# Main_board.net
KiCad netlist of a schematic drawn in EAGLE
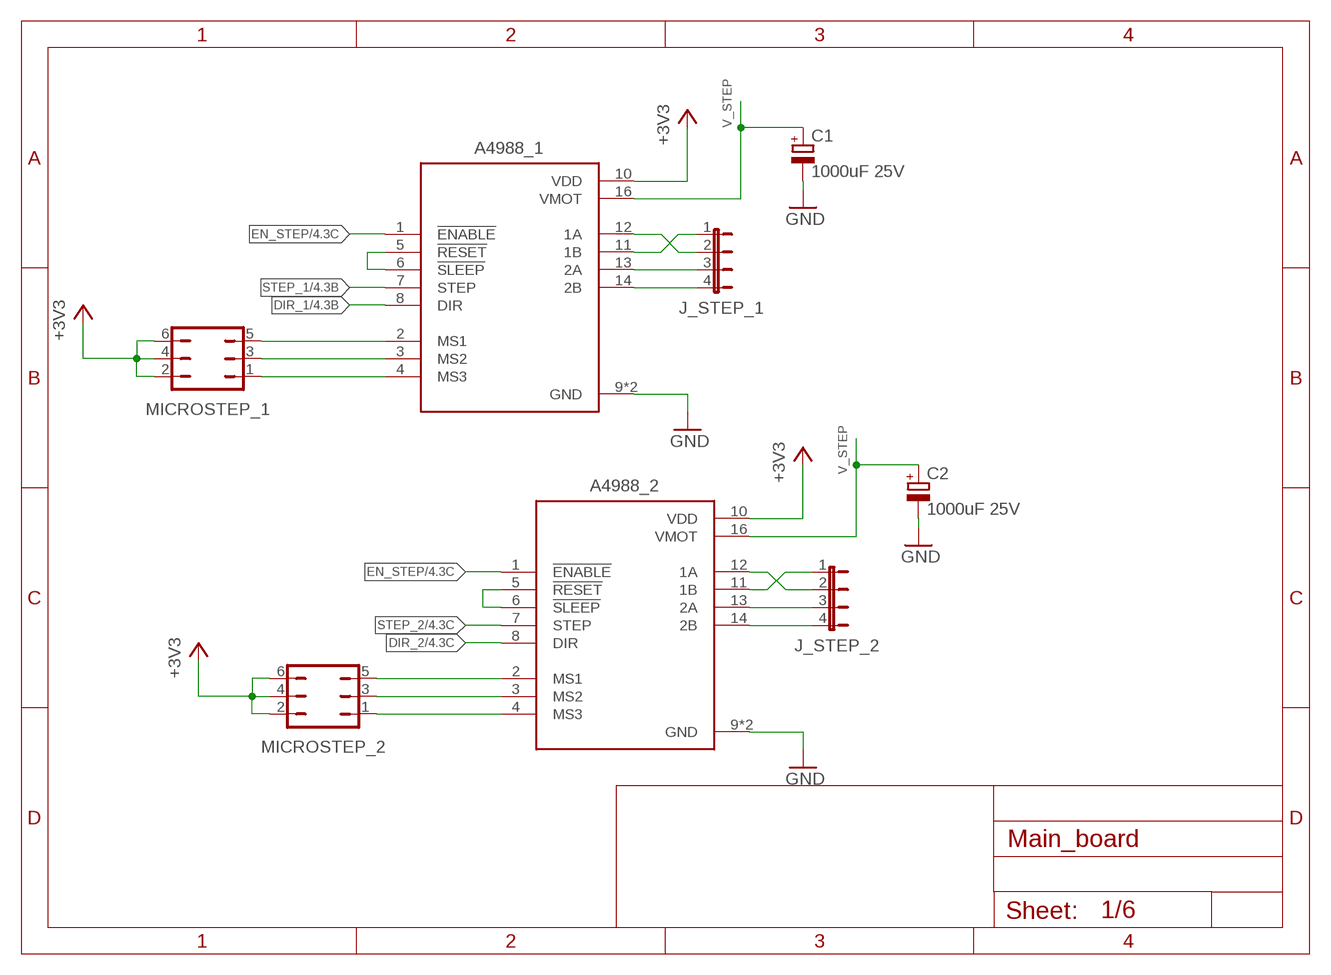
[diagram p0: schematic, sheet 1]
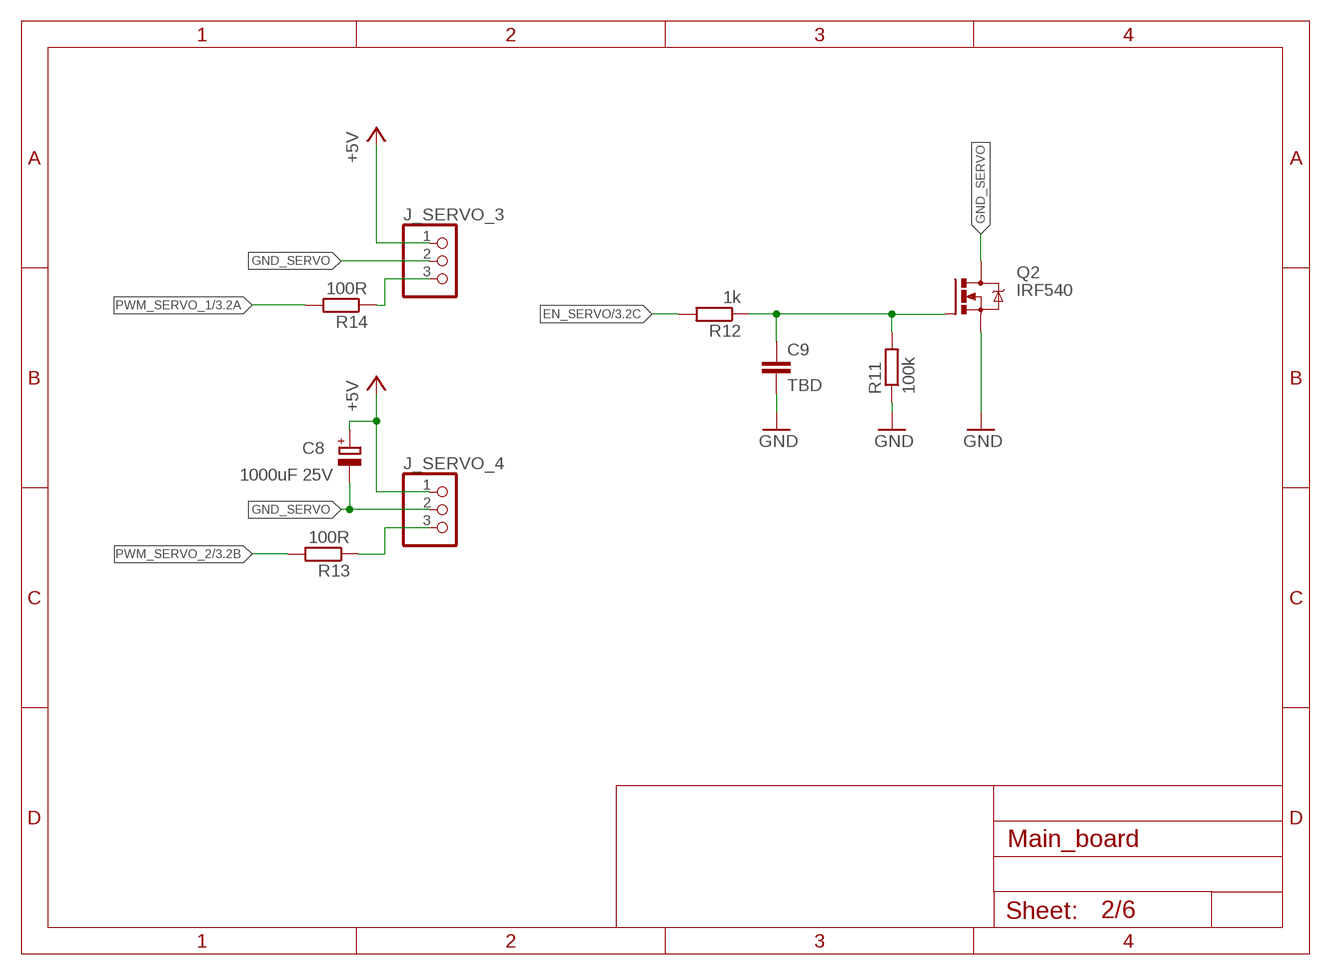
[diagram p1: schematic, sheet 2]
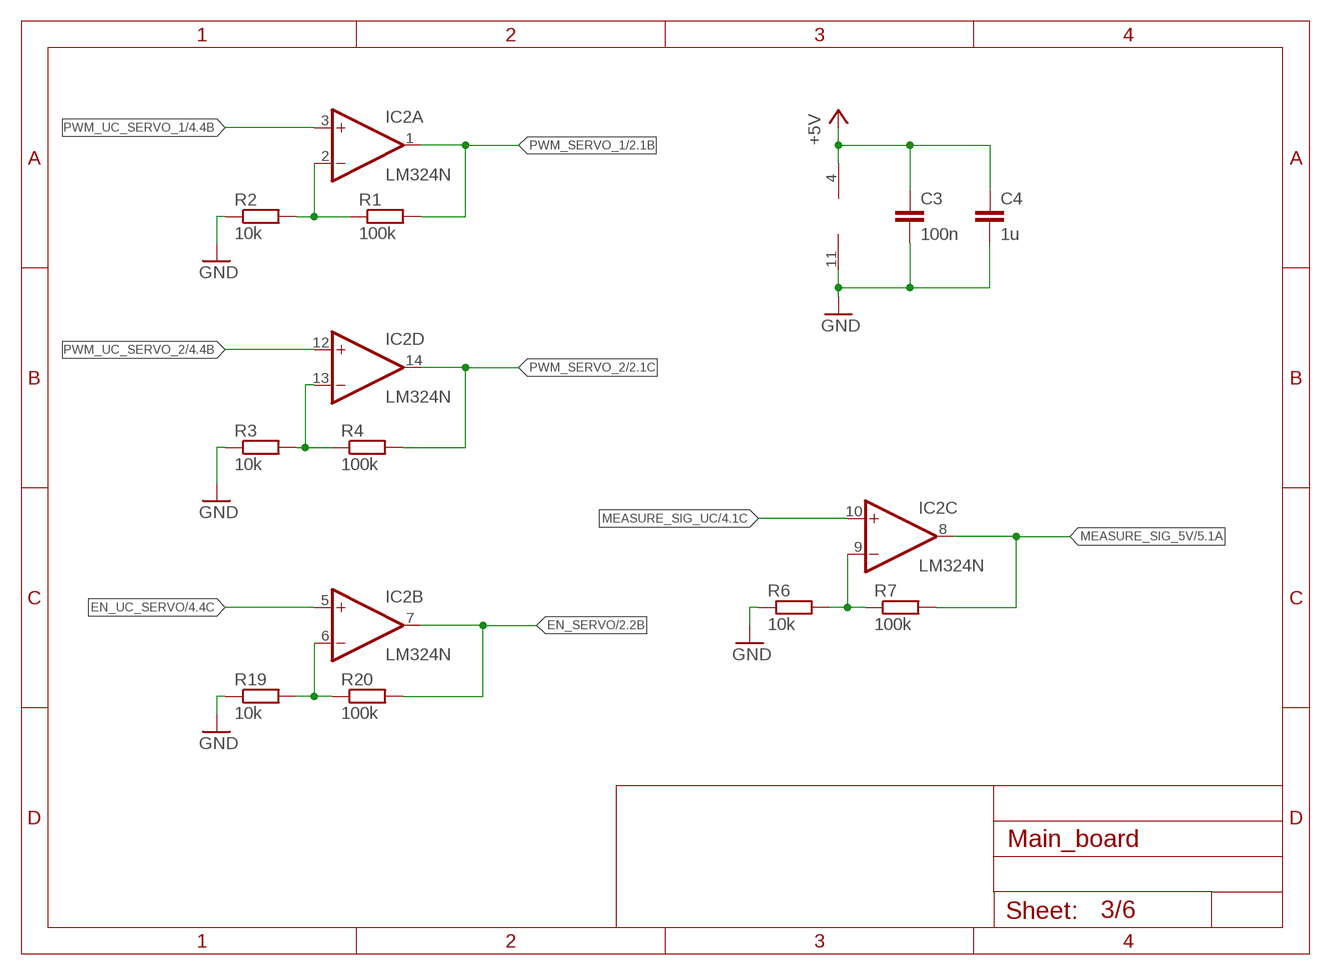
[diagram p2: schematic, sheet 3]
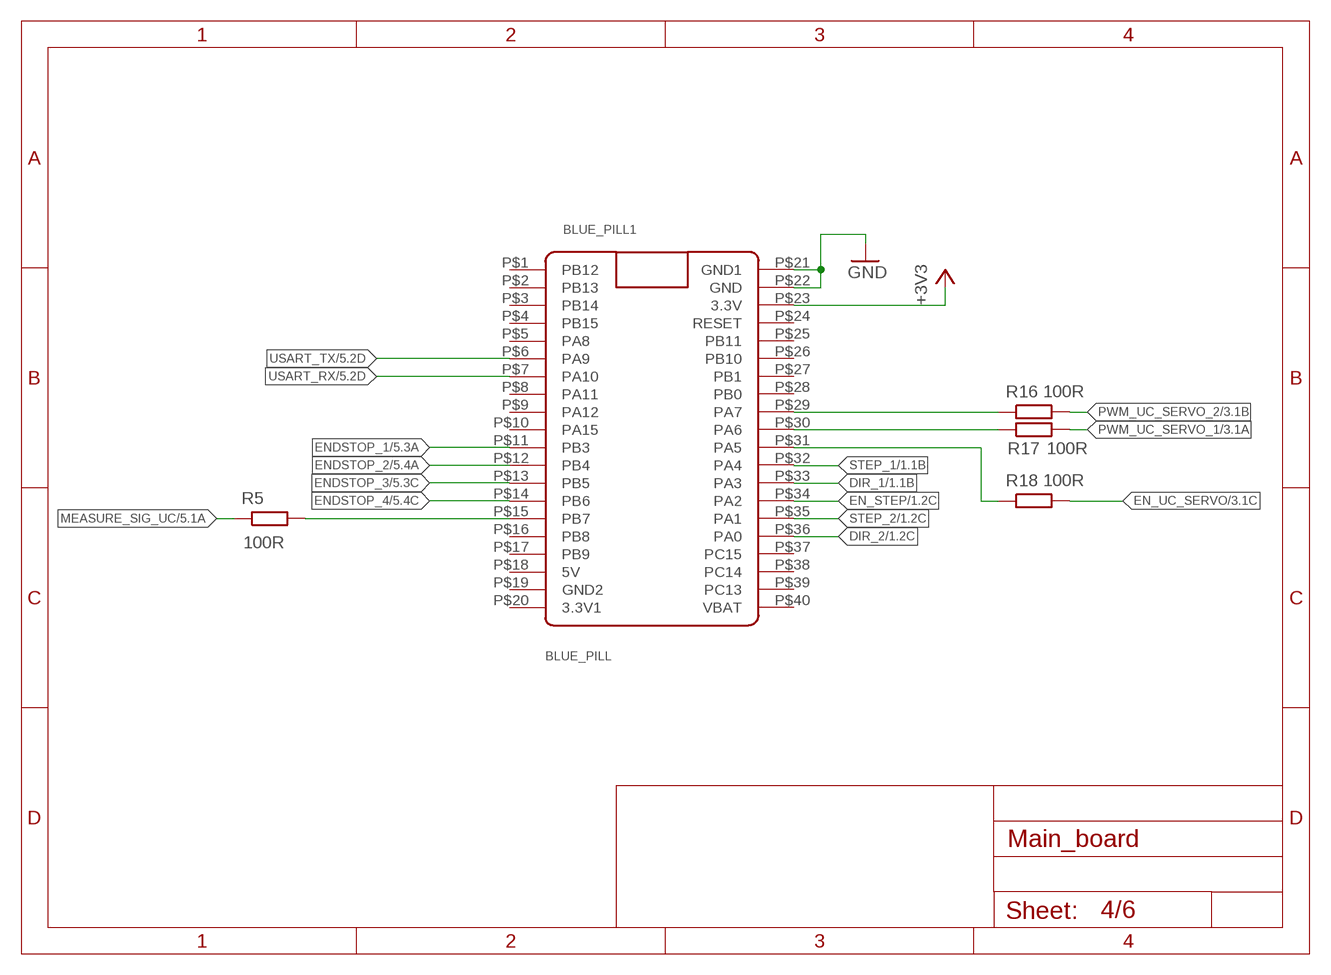
[diagram p3: schematic, sheet 4]
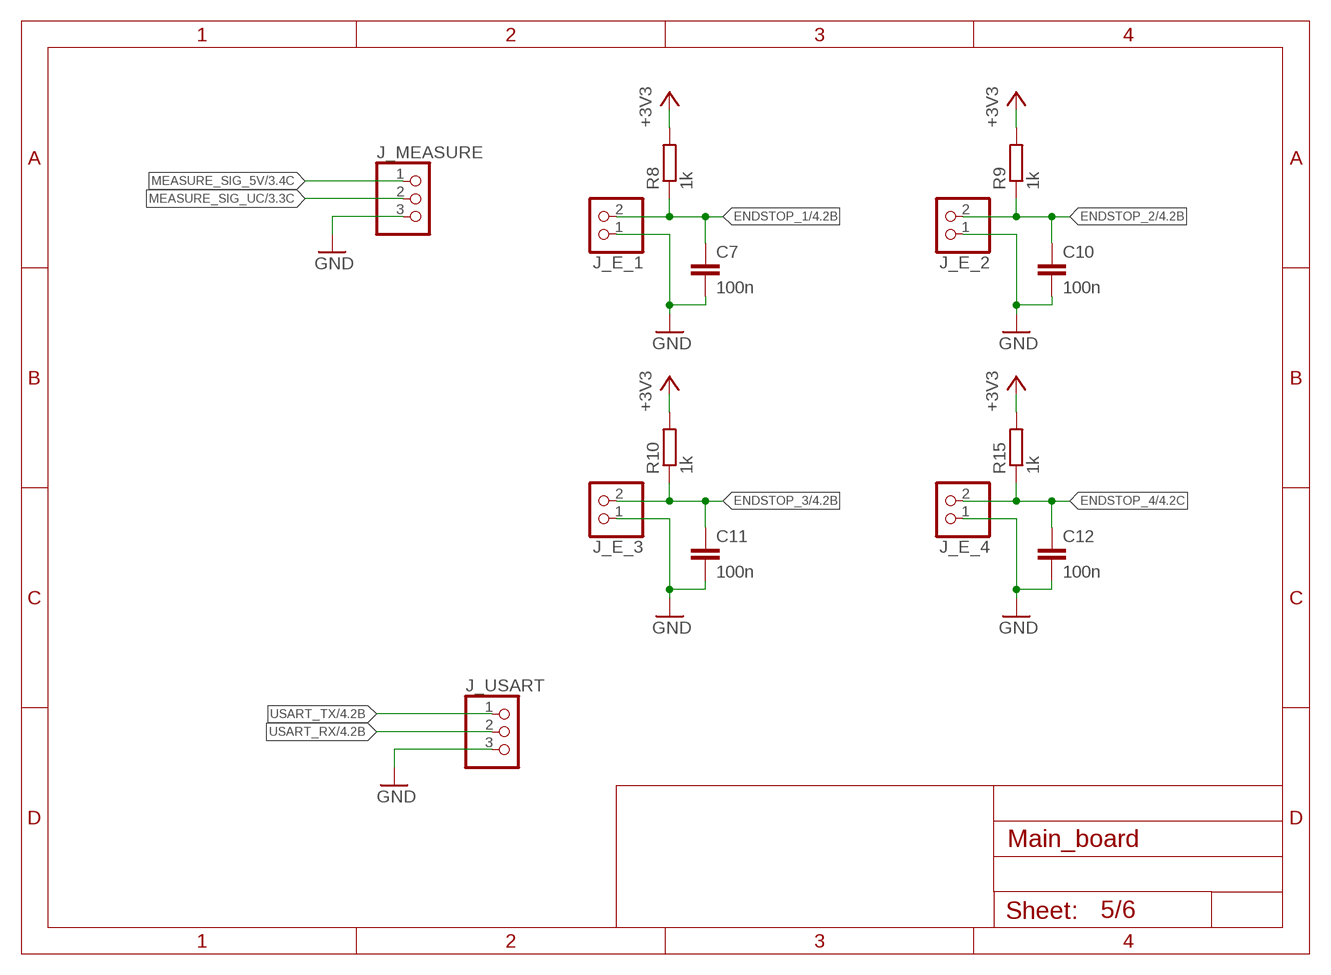
[diagram p4: schematic, sheet 5]
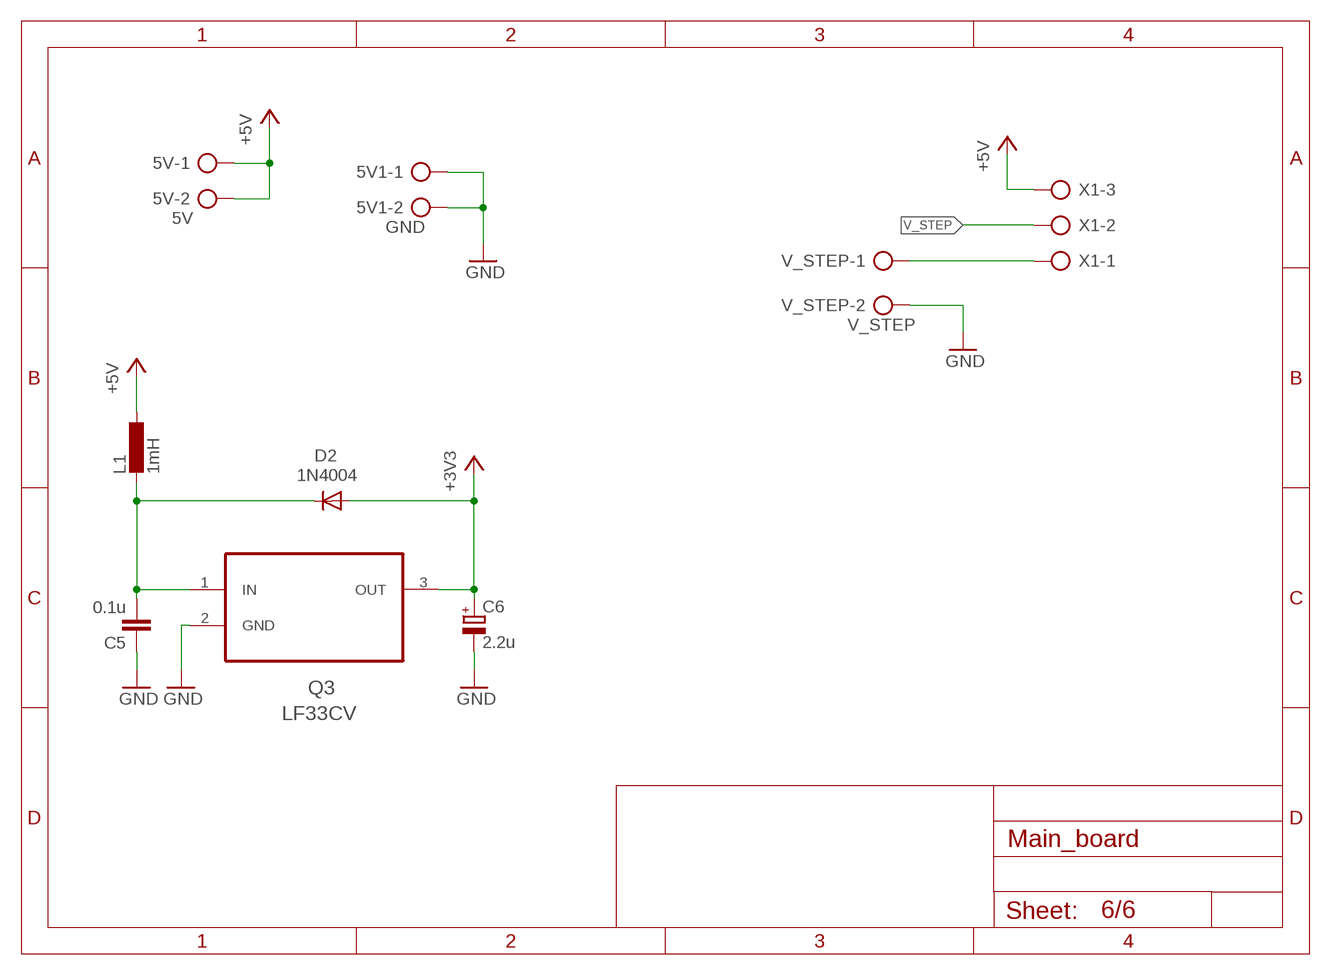
[diagram p5: schematic, sheet 6]

(export (version "E")
  (design (tool "Eeschema 10.0.6"))
  (components
    (comp (ref "BLUE_PILL1")
      (value "BLUE_PILL")
      (footprint "eagle-import:BLUE_PILL")
      (libsource (lib "eagle-import") (part "BLUE_PILL"))
    )
    (comp (ref "R5")
      (value "100R")
      (footprint "eagle-import:R3216")
      (libsource (lib "eagle-import") (part "R-EU_R3216"))
    )
    (comp (ref "R16")
      (value "100R")
      (footprint "eagle-import:R3216")
      (libsource (lib "eagle-import") (part "R-EU_R3216"))
    )
    (comp (ref "R17")
      (value "100R")
      (footprint "eagle-import:R3216")
      (libsource (lib "eagle-import") (part "R-EU_R3216"))
    )
    (comp (ref "R18")
      (value "100R")
      (footprint "eagle-import:R3216")
      (libsource (lib "eagle-import") (part "R-EU_R3216"))
    )
    (comp (ref "A4988_1")
      (value "A4988_STEPPER_MOTOR_DRIVER_CARRIER")
      (footprint "eagle-import:MODULE_A4988_STEPPER_MOTOR_DRIVER_CARRIER")
      (fields (field (name "MF") "Pololu") (field (name "MP") "A4988 STEPPER MOTOR DRIVER CARRIER"))
      (libsource (lib "eagle-import") (part "A4988_STEPPER_MOTOR_DRIVER_CARRIER"))
    )
    (comp (ref "A4988_2")
      (value "A4988_STEPPER_MOTOR_DRIVER_CARRIER")
      (footprint "eagle-import:MODULE_A4988_STEPPER_MOTOR_DRIVER_CARRIER")
      (fields (field (name "MF") "Pololu") (field (name "MP") "A4988 STEPPER MOTOR DRIVER CARRIER"))
      (libsource (lib "eagle-import") (part "A4988_STEPPER_MOTOR_DRIVER_CARRIER"))
    )
    (comp (ref "C1")
      (value "1000uF 25V")
      (footprint "eagle-import:E3,5-10")
      (libsource (lib "eagle-import") (part "CPOL-EUE3.5-10"))
    )
    (comp (ref "C2")
      (value "1000uF 25V")
      (footprint "eagle-import:E3,5-10")
      (libsource (lib "eagle-import") (part "CPOL-EUE3.5-10"))
    )
    (comp (ref "J_STEP_1")
      (value "JP4E")
      (footprint "eagle-import:JP4")
      (libsource (lib "eagle-import") (part "JP4E"))
    )
    (comp (ref "J_STEP_2")
      (value "JP4E")
      (footprint "eagle-import:JP4")
      (libsource (lib "eagle-import") (part "JP4E"))
    )
    (comp (ref "MICROSTEP_1")
      (value "JP3Q")
      (footprint "eagle-import:JP3Q")
      (libsource (lib "eagle-import") (part "JP3Q"))
    )
    (comp (ref "MICROSTEP_2")
      (value "JP3Q")
      (footprint "eagle-import:JP3Q")
      (libsource (lib "eagle-import") (part "JP3Q"))
    )
    (comp (ref "C7")
      (value "100n")
      (footprint "eagle-import:C0402")
      (libsource (lib "eagle-import") (part "C-EUC0402"))
    )
    (comp (ref "C10")
      (value "100n")
      (footprint "eagle-import:C0402")
      (libsource (lib "eagle-import") (part "C-EUC0402"))
    )
    (comp (ref "C11")
      (value "100n")
      (footprint "eagle-import:C0402")
      (libsource (lib "eagle-import") (part "C-EUC0402"))
    )
    (comp (ref "C12")
      (value "100n")
      (footprint "eagle-import:C0402")
      (libsource (lib "eagle-import") (part "C-EUC0402"))
    )
    (comp (ref "J_E_1")
      (value "PINHD-1X2")
      (footprint "eagle-import:1X02")
      (libsource (lib "eagle-import") (part "PINHD-1X2"))
    )
    (comp (ref "J_E_2")
      (value "PINHD-1X2")
      (footprint "eagle-import:1X02")
      (libsource (lib "eagle-import") (part "PINHD-1X2"))
    )
    (comp (ref "J_E_3")
      (value "PINHD-1X2")
      (footprint "eagle-import:1X02")
      (libsource (lib "eagle-import") (part "PINHD-1X2"))
    )
    (comp (ref "J_E_4")
      (value "PINHD-1X2")
      (footprint "eagle-import:1X02")
      (libsource (lib "eagle-import") (part "PINHD-1X2"))
    )
    (comp (ref "J_MEASURE")
      (value "PINHD-1X3")
      (footprint "eagle-import:1X03")
      (libsource (lib "eagle-import") (part "PINHD-1X3"))
    )
    (comp (ref "J_USART")
      (value "PINHD-1X3")
      (footprint "eagle-import:1X03")
      (libsource (lib "eagle-import") (part "PINHD-1X3"))
    )
    (comp (ref "R8")
      (value "1k")
      (footprint "eagle-import:R3216")
      (libsource (lib "eagle-import") (part "R-EU_R3216"))
    )
    (comp (ref "R9")
      (value "1k")
      (footprint "eagle-import:R3216")
      (libsource (lib "eagle-import") (part "R-EU_R3216"))
    )
    (comp (ref "R10")
      (value "1k")
      (footprint "eagle-import:R3216")
      (libsource (lib "eagle-import") (part "R-EU_R3216"))
    )
    (comp (ref "R15")
      (value "1k")
      (footprint "eagle-import:R3216")
      (libsource (lib "eagle-import") (part "R-EU_R3216"))
    )
    (comp (ref "C8")
      (value "1000uF 25V")
      (footprint "eagle-import:E3,5-10")
      (libsource (lib "eagle-import") (part "CPOL-EUE3.5-10"))
    )
    (comp (ref "C9")
      (value "TBD")
      (footprint "eagle-import:C3216")
      (libsource (lib "eagle-import") (part "C-EUC3216"))
    )
    (comp (ref "J_SERVO_3")
      (value "PINHD-1X3")
      (footprint "eagle-import:1X03")
      (libsource (lib "eagle-import") (part "PINHD-1X3"))
    )
    (comp (ref "J_SERVO_4")
      (value "PINHD-1X3")
      (footprint "eagle-import:1X03")
      (libsource (lib "eagle-import") (part "PINHD-1X3"))
    )
    (comp (ref "Q2")
      (value "IRF540")
      (footprint "eagle-import:TO220BV")
      (libsource (lib "eagle-import") (part "IRF540"))
    )
    (comp (ref "R11")
      (value "100k")
      (footprint "eagle-import:R3216")
      (libsource (lib "eagle-import") (part "R-EU_R3216"))
    )
    (comp (ref "R12")
      (value "1k")
      (footprint "eagle-import:R3216")
      (libsource (lib "eagle-import") (part "R-EU_R3216"))
    )
    (comp (ref "R13")
      (value "100R")
      (footprint "eagle-import:R3216")
      (libsource (lib "eagle-import") (part "R-EU_R3216"))
    )
    (comp (ref "R14")
      (value "100R")
      (footprint "eagle-import:R3216")
      (libsource (lib "eagle-import") (part "R-EU_R3216"))
    )
    (comp (ref "C3")
      (value "100n")
      (footprint "eagle-import:C2012")
      (libsource (lib "eagle-import") (part "C-EUC2012"))
    )
    (comp (ref "C4")
      (value "1u")
      (footprint "eagle-import:C2012")
      (libsource (lib "eagle-import") (part "C-EUC2012"))
    )
    (comp (ref "IC2")
      (value "LM324N")
      (footprint "eagle-import:DIL14")
      (libsource (lib "eagle-import") (part "LM324N"))
    )
    (comp (ref "R1")
      (value "100k")
      (footprint "eagle-import:R3216")
      (libsource (lib "eagle-import") (part "R-EU_R3216"))
    )
    (comp (ref "R2")
      (value "10k")
      (footprint "eagle-import:R3216")
      (libsource (lib "eagle-import") (part "R-EU_R3216"))
    )
    (comp (ref "R3")
      (value "10k")
      (footprint "eagle-import:R3216")
      (libsource (lib "eagle-import") (part "R-EU_R3216"))
    )
    (comp (ref "R4")
      (value "100k")
      (footprint "eagle-import:R3216")
      (libsource (lib "eagle-import") (part "R-EU_R3216"))
    )
    (comp (ref "R6")
      (value "10k")
      (footprint "eagle-import:R3216")
      (libsource (lib "eagle-import") (part "R-EU_R3216"))
    )
    (comp (ref "R7")
      (value "100k")
      (footprint "eagle-import:R3216")
      (libsource (lib "eagle-import") (part "R-EU_R3216"))
    )
    (comp (ref "R19")
      (value "10k")
      (footprint "eagle-import:R3216")
      (libsource (lib "eagle-import") (part "R-EU_R3216"))
    )
    (comp (ref "R20")
      (value "100k")
      (footprint "eagle-import:R3216")
      (libsource (lib "eagle-import") (part "R-EU_R3216"))
    )
    (comp (ref "5V")
      (value "5V")
      (footprint "eagle-import:AK500_2")
      (libsource (lib "eagle-import") (part "AK500/2"))
    )
    (comp (ref "5V1")
      (value "GND")
      (footprint "eagle-import:AK500_2")
      (libsource (lib "eagle-import") (part "AK500/2"))
    )
    (comp (ref "C5")
      (value "0.1u")
      (footprint "eagle-import:C3216")
      (libsource (lib "eagle-import") (part "C-EUC3216"))
    )
    (comp (ref "C6")
      (value "2.2u")
      (footprint "eagle-import:E2,5-5")
      (libsource (lib "eagle-import") (part "CPOL-EUE2.5-5"))
    )
    (comp (ref "D2")
      (value "1N4004")
      (footprint "eagle-import:DO41-10")
      (libsource (lib "eagle-import") (part "1N4004"))
    )
    (comp (ref "L1")
      (value "1mH")
      (footprint "eagle-import:POWER-CHOKE_WE-TPC")
      (libsource (lib "eagle-import") (part "L-EUWE-TPC"))
    )
    (comp (ref "Q3")
      (value "LF33CV")
      (footprint "eagle-import:TO254P450X1020X1935-3P")
      (fields (field (name "MF") "STMicroelectronics"))
      (libsource (lib "eagle-import") (part "LF33CV"))
    )
    (comp (ref "V_STEP")
      (value "V_STEP")
      (footprint "eagle-import:AK500_2")
      (libsource (lib "eagle-import") (part "AK500/2"))
    )
    (comp (ref "X1")
      (value "AK500/3-H")
      (footprint "eagle-import:AK500_3-H")
      (libsource (lib "eagle-import") (part "AK500/3-H"))
    )
  )
  (nets
    (net (code "1") (name "+3V3") (class "Default")
      (node (ref "A4988_1") (pin "10") (pinfunction "VDD_10") (pintype "power_in"))
      (node (ref "A4988_2") (pin "10") (pinfunction "VDD_10") (pintype "power_in"))
      (node (ref "BLUE_PILL1") (pin "P$23") (pinfunction "3.3V_P$23") (pintype "bidirectional"))
      (node (ref "C6") (pin "+") (pinfunction "+_+") (pintype "passive"))
      (node (ref "D2") (pin "A") (pinfunction "A_A") (pintype "passive"))
      (node (ref "MICROSTEP_1") (pin "2") (pinfunction "2_2") (pintype "passive"))
      (node (ref "MICROSTEP_1") (pin "4") (pinfunction "4_4") (pintype "passive"))
      (node (ref "MICROSTEP_1") (pin "6") (pinfunction "6_6") (pintype "passive"))
      (node (ref "MICROSTEP_2") (pin "2") (pinfunction "2_2") (pintype "passive"))
      (node (ref "MICROSTEP_2") (pin "4") (pinfunction "4_4") (pintype "passive"))
      (node (ref "MICROSTEP_2") (pin "6") (pinfunction "6_6") (pintype "passive"))
      (node (ref "Q3") (pin "3") (pinfunction "OUT_3") (pintype "output"))
      (node (ref "R10") (pin "2") (pinfunction "2_2") (pintype "passive"))
      (node (ref "R15") (pin "2") (pinfunction "2_2") (pintype "passive"))
      (node (ref "R8") (pin "2") (pinfunction "2_2") (pintype "passive"))
      (node (ref "R9") (pin "2") (pinfunction "2_2") (pintype "passive"))
    )
    (net (code "2") (name "+5V") (class "Default")
      (node (ref "5V") (pin "1") (pinfunction "KL_1") (pintype "passive"))
      (node (ref "5V") (pin "2") (pinfunction "KL_2") (pintype "passive"))
      (node (ref "C3") (pin "1") (pinfunction "1_1") (pintype "passive"))
      (node (ref "C4") (pin "1") (pinfunction "1_1") (pintype "passive"))
      (node (ref "C8") (pin "+") (pinfunction "+_+") (pintype "passive"))
      (node (ref "IC2") (pin "4") (pinfunction "V+_4") (pintype "power_in"))
      (node (ref "J_SERVO_3") (pin "1") (pinfunction "1_1") (pintype "passive"))
      (node (ref "J_SERVO_4") (pin "1") (pinfunction "1_1") (pintype "passive"))
      (node (ref "L1") (pin "1") (pinfunction "1_1") (pintype "passive"))
      (node (ref "X1") (pin "3") (pinfunction "KL_3") (pintype "passive"))
    )
    (net (code "3") (name "DIR_1") (class "Default")
      (node (ref "A4988_1") (pin "8") (pinfunction "DIR_8") (pintype "input"))
      (node (ref "BLUE_PILL1") (pin "P$33") (pinfunction "PA3_P$33") (pintype "bidirectional"))
    )
    (net (code "4") (name "DIR_2") (class "Default")
      (node (ref "A4988_2") (pin "8") (pinfunction "DIR_8") (pintype "input"))
      (node (ref "BLUE_PILL1") (pin "P$36") (pinfunction "PA0_P$36") (pintype "bidirectional"))
    )
    (net (code "5") (name "ENDSTOP_1") (class "Default")
      (node (ref "BLUE_PILL1") (pin "P$11") (pinfunction "PB3_P$11") (pintype "bidirectional"))
      (node (ref "C7") (pin "1") (pinfunction "1_1") (pintype "passive"))
      (node (ref "J_E_1") (pin "2") (pinfunction "2_2") (pintype "passive"))
      (node (ref "R8") (pin "1") (pinfunction "1_1") (pintype "passive"))
    )
    (net (code "6") (name "ENDSTOP_2") (class "Default")
      (node (ref "BLUE_PILL1") (pin "P$12") (pinfunction "PB4_P$12") (pintype "bidirectional"))
      (node (ref "C10") (pin "1") (pinfunction "1_1") (pintype "passive"))
      (node (ref "J_E_2") (pin "2") (pinfunction "2_2") (pintype "passive"))
      (node (ref "R9") (pin "1") (pinfunction "1_1") (pintype "passive"))
    )
    (net (code "7") (name "ENDSTOP_3") (class "Default")
      (node (ref "BLUE_PILL1") (pin "P$13") (pinfunction "PB5_P$13") (pintype "bidirectional"))
      (node (ref "C11") (pin "1") (pinfunction "1_1") (pintype "passive"))
      (node (ref "J_E_3") (pin "2") (pinfunction "2_2") (pintype "passive"))
      (node (ref "R10") (pin "1") (pinfunction "1_1") (pintype "passive"))
    )
    (net (code "8") (name "ENDSTOP_4") (class "Default")
      (node (ref "BLUE_PILL1") (pin "P$14") (pinfunction "PB6_P$14") (pintype "bidirectional"))
      (node (ref "C12") (pin "1") (pinfunction "1_1") (pintype "passive"))
      (node (ref "J_E_4") (pin "2") (pinfunction "2_2") (pintype "passive"))
      (node (ref "R15") (pin "1") (pinfunction "1_1") (pintype "passive"))
    )
    (net (code "9") (name "EN_SERVO") (class "Default")
      (node (ref "IC2") (pin "7") (pinfunction "OUT_7") (pintype "output"))
      (node (ref "R12") (pin "2") (pinfunction "2_2") (pintype "passive"))
      (node (ref "R20") (pin "2") (pinfunction "2_2") (pintype "passive"))
    )
    (net (code "10") (name "EN_STEP") (class "Default")
      (node (ref "A4988_1") (pin "1") (pinfunction "~{ENABLE}_1") (pintype "input"))
      (node (ref "A4988_2") (pin "1") (pinfunction "~{ENABLE}_1") (pintype "input"))
      (node (ref "BLUE_PILL1") (pin "P$34") (pinfunction "PA2_P$34") (pintype "bidirectional"))
    )
    (net (code "11") (name "EN_UC_SERVO") (class "Default")
      (node (ref "IC2") (pin "5") (pinfunction "+IN_5") (pintype "input"))
      (node (ref "R18") (pin "2") (pinfunction "2_2") (pintype "passive"))
    )
    (net (code "12") (name "GND") (class "Default")
      (node (ref "5V1") (pin "1") (pinfunction "KL_1") (pintype "passive"))
      (node (ref "5V1") (pin "2") (pinfunction "KL_2") (pintype "passive"))
      (node (ref "A4988_1") (pin "15") (pinfunction "GND_15") (pintype "power_in"))
      (node (ref "A4988_1") (pin "9") (pinfunction "GND_9") (pintype "power_in"))
      (node (ref "A4988_2") (pin "15") (pinfunction "GND_15") (pintype "power_in"))
      (node (ref "A4988_2") (pin "9") (pinfunction "GND_9") (pintype "power_in"))
      (node (ref "BLUE_PILL1") (pin "P$21") (pinfunction "GND1_P$21") (pintype "power_in"))
      (node (ref "BLUE_PILL1") (pin "P$22") (pinfunction "GND_P$22") (pintype "bidirectional"))
      (node (ref "C1") (pin "-") (pinfunction "-_-") (pintype "passive"))
      (node (ref "C10") (pin "2") (pinfunction "2_2") (pintype "passive"))
      (node (ref "C11") (pin "2") (pinfunction "2_2") (pintype "passive"))
      (node (ref "C12") (pin "2") (pinfunction "2_2") (pintype "passive"))
      (node (ref "C2") (pin "-") (pinfunction "-_-") (pintype "passive"))
      (node (ref "C3") (pin "2") (pinfunction "2_2") (pintype "passive"))
      (node (ref "C4") (pin "2") (pinfunction "2_2") (pintype "passive"))
      (node (ref "C5") (pin "1") (pinfunction "1_1") (pintype "passive"))
      (node (ref "C6") (pin "-") (pinfunction "-_-") (pintype "passive"))
      (node (ref "C7") (pin "2") (pinfunction "2_2") (pintype "passive"))
      (node (ref "C9") (pin "2") (pinfunction "2_2") (pintype "passive"))
      (node (ref "IC2") (pin "11") (pinfunction "V-_11") (pintype "power_in"))
      (node (ref "J_E_1") (pin "1") (pinfunction "1_1") (pintype "passive"))
      (node (ref "J_E_2") (pin "1") (pinfunction "1_1") (pintype "passive"))
      (node (ref "J_E_3") (pin "1") (pinfunction "1_1") (pintype "passive"))
      (node (ref "J_E_4") (pin "1") (pinfunction "1_1") (pintype "passive"))
      (node (ref "J_MEASURE") (pin "3") (pinfunction "3_3") (pintype "passive"))
      (node (ref "J_USART") (pin "3") (pinfunction "3_3") (pintype "passive"))
      (node (ref "Q2") (pin "S") (pinfunction "S_S") (pintype "passive"))
      (node (ref "Q3") (pin "2") (pinfunction "GND_2") (pintype "passive"))
      (node (ref "R11") (pin "1") (pinfunction "1_1") (pintype "passive"))
      (node (ref "R19") (pin "1") (pinfunction "1_1") (pintype "passive"))
      (node (ref "R2") (pin "1") (pinfunction "1_1") (pintype "passive"))
      (node (ref "R3") (pin "1") (pinfunction "1_1") (pintype "passive"))
      (node (ref "R6") (pin "1") (pinfunction "1_1") (pintype "passive"))
      (node (ref "V_STEP") (pin "2") (pinfunction "KL_2") (pintype "passive"))
    )
    (net (code "13") (name "GND_SERVO") (class "Default")
      (node (ref "C8") (pin "-") (pinfunction "-_-") (pintype "passive"))
      (node (ref "J_SERVO_3") (pin "2") (pinfunction "2_2") (pintype "passive"))
      (node (ref "J_SERVO_4") (pin "2") (pinfunction "2_2") (pintype "passive"))
      (node (ref "Q2") (pin "D") (pinfunction "D_D") (pintype "passive"))
    )
    (net (code "14") (name "MEASURE_SIG_5V") (class "Default")
      (node (ref "IC2") (pin "8") (pinfunction "OUT_8") (pintype "output"))
      (node (ref "J_MEASURE") (pin "1") (pinfunction "1_1") (pintype "passive"))
      (node (ref "R7") (pin "2") (pinfunction "2_2") (pintype "passive"))
    )
    (net (code "15") (name "MEASURE_SIG_UC") (class "Default")
      (node (ref "IC2") (pin "10") (pinfunction "+IN_10") (pintype "input"))
      (node (ref "J_MEASURE") (pin "2") (pinfunction "2_2") (pintype "passive"))
      (node (ref "R5") (pin "1") (pinfunction "1_1") (pintype "passive"))
    )
    (net (code "16") (name "Net-(A4988_1-1A)") (class "Default")
      (node (ref "A4988_1") (pin "12") (pinfunction "1A_12") (pintype "output"))
      (node (ref "J_STEP_1") (pin "2") (pinfunction "2_2") (pintype "passive"))
    )
    (net (code "17") (name "Net-(A4988_1-1B)") (class "Default")
      (node (ref "A4988_1") (pin "11") (pinfunction "1B_11") (pintype "output"))
      (node (ref "J_STEP_1") (pin "1") (pinfunction "1_1") (pintype "passive"))
    )
    (net (code "18") (name "Net-(A4988_1-2A)") (class "Default")
      (node (ref "A4988_1") (pin "13") (pinfunction "2A_13") (pintype "output"))
      (node (ref "J_STEP_1") (pin "3") (pinfunction "3_3") (pintype "passive"))
    )
    (net (code "19") (name "Net-(A4988_1-2B)") (class "Default")
      (node (ref "A4988_1") (pin "14") (pinfunction "2B_14") (pintype "output"))
      (node (ref "J_STEP_1") (pin "4") (pinfunction "4_4") (pintype "passive"))
    )
    (net (code "20") (name "Net-(A4988_1-MS1)") (class "Default")
      (node (ref "A4988_1") (pin "2") (pinfunction "MS1_2") (pintype "input"))
      (node (ref "MICROSTEP_1") (pin "5") (pinfunction "5_5") (pintype "passive"))
    )
    (net (code "21") (name "Net-(A4988_1-MS2)") (class "Default")
      (node (ref "A4988_1") (pin "3") (pinfunction "MS2_3") (pintype "input"))
      (node (ref "MICROSTEP_1") (pin "3") (pinfunction "3_3") (pintype "passive"))
    )
    (net (code "22") (name "Net-(A4988_1-MS3)") (class "Default")
      (node (ref "A4988_1") (pin "4") (pinfunction "MS3_4") (pintype "input"))
      (node (ref "MICROSTEP_1") (pin "1") (pinfunction "1_1") (pintype "passive"))
    )
    (net (code "23") (name "Net-(A4988_1-~{RESET})") (class "Default")
      (node (ref "A4988_1") (pin "5") (pinfunction "~{RESET}_5") (pintype "input"))
      (node (ref "A4988_1") (pin "6") (pinfunction "~{SLEEP}_6") (pintype "input"))
    )
    (net (code "24") (name "Net-(A4988_2-1A)") (class "Default")
      (node (ref "A4988_2") (pin "12") (pinfunction "1A_12") (pintype "output"))
      (node (ref "J_STEP_2") (pin "2") (pinfunction "2_2") (pintype "passive"))
    )
    (net (code "25") (name "Net-(A4988_2-1B)") (class "Default")
      (node (ref "A4988_2") (pin "11") (pinfunction "1B_11") (pintype "output"))
      (node (ref "J_STEP_2") (pin "1") (pinfunction "1_1") (pintype "passive"))
    )
    (net (code "26") (name "Net-(A4988_2-2A)") (class "Default")
      (node (ref "A4988_2") (pin "13") (pinfunction "2A_13") (pintype "output"))
      (node (ref "J_STEP_2") (pin "3") (pinfunction "3_3") (pintype "passive"))
    )
    (net (code "27") (name "Net-(A4988_2-2B)") (class "Default")
      (node (ref "A4988_2") (pin "14") (pinfunction "2B_14") (pintype "output"))
      (node (ref "J_STEP_2") (pin "4") (pinfunction "4_4") (pintype "passive"))
    )
    (net (code "28") (name "Net-(A4988_2-MS1)") (class "Default")
      (node (ref "A4988_2") (pin "2") (pinfunction "MS1_2") (pintype "input"))
      (node (ref "MICROSTEP_2") (pin "5") (pinfunction "5_5") (pintype "passive"))
    )
    (net (code "29") (name "Net-(A4988_2-MS2)") (class "Default")
      (node (ref "A4988_2") (pin "3") (pinfunction "MS2_3") (pintype "input"))
      (node (ref "MICROSTEP_2") (pin "3") (pinfunction "3_3") (pintype "passive"))
    )
    (net (code "30") (name "Net-(A4988_2-MS3)") (class "Default")
      (node (ref "A4988_2") (pin "4") (pinfunction "MS3_4") (pintype "input"))
      (node (ref "MICROSTEP_2") (pin "1") (pinfunction "1_1") (pintype "passive"))
    )
    (net (code "31") (name "Net-(A4988_2-~{RESET})") (class "Default")
      (node (ref "A4988_2") (pin "5") (pinfunction "~{RESET}_5") (pintype "input"))
      (node (ref "A4988_2") (pin "6") (pinfunction "~{SLEEP}_6") (pintype "input"))
    )
    (net (code "32") (name "Net-(BLUE_PILL1-PA5)") (class "Default")
      (node (ref "BLUE_PILL1") (pin "P$31") (pinfunction "PA5_P$31") (pintype "bidirectional"))
      (node (ref "R18") (pin "1") (pinfunction "1_1") (pintype "passive"))
    )
    (net (code "33") (name "Net-(BLUE_PILL1-PA6)") (class "Default")
      (node (ref "BLUE_PILL1") (pin "P$30") (pinfunction "PA6_P$30") (pintype "bidirectional"))
      (node (ref "R17") (pin "1") (pinfunction "1_1") (pintype "passive"))
    )
    (net (code "34") (name "Net-(BLUE_PILL1-PA7)") (class "Default")
      (node (ref "BLUE_PILL1") (pin "P$29") (pinfunction "PA7_P$29") (pintype "bidirectional"))
      (node (ref "R16") (pin "1") (pinfunction "1_1") (pintype "passive"))
    )
    (net (code "35") (name "Net-(BLUE_PILL1-PB7)") (class "Default")
      (node (ref "BLUE_PILL1") (pin "P$15") (pinfunction "PB7_P$15") (pintype "bidirectional"))
      (node (ref "R5") (pin "2") (pinfunction "2_2") (pintype "passive"))
    )
    (net (code "36") (name "Net-(C9-Pad1)") (class "Default")
      (node (ref "C9") (pin "1") (pinfunction "1_1") (pintype "passive"))
      (node (ref "Q2") (pin "G") (pinfunction "G_G") (pintype "passive"))
      (node (ref "R11") (pin "2") (pinfunction "2_2") (pintype "passive"))
      (node (ref "R12") (pin "1") (pinfunction "1_1") (pintype "passive"))
    )
    (net (code "37") (name "Net-(IC2A--IN)") (class "Default")
      (node (ref "IC2") (pin "2") (pinfunction "-IN_2") (pintype "input"))
      (node (ref "R1") (pin "1") (pinfunction "1_1") (pintype "passive"))
      (node (ref "R2") (pin "2") (pinfunction "2_2") (pintype "passive"))
    )
    (net (code "38") (name "Net-(IC2B--IN)") (class "Default")
      (node (ref "IC2") (pin "6") (pinfunction "-IN_6") (pintype "input"))
      (node (ref "R19") (pin "2") (pinfunction "2_2") (pintype "passive"))
      (node (ref "R20") (pin "1") (pinfunction "1_1") (pintype "passive"))
    )
    (net (code "39") (name "Net-(IC2C--IN)") (class "Default")
      (node (ref "IC2") (pin "9") (pinfunction "-IN_9") (pintype "input"))
      (node (ref "R6") (pin "2") (pinfunction "2_2") (pintype "passive"))
      (node (ref "R7") (pin "1") (pinfunction "1_1") (pintype "passive"))
    )
    (net (code "40") (name "Net-(IC2D--IN)") (class "Default")
      (node (ref "IC2") (pin "13") (pinfunction "-IN_13") (pintype "input"))
      (node (ref "R3") (pin "2") (pinfunction "2_2") (pintype "passive"))
      (node (ref "R4") (pin "1") (pinfunction "1_1") (pintype "passive"))
    )
    (net (code "41") (name "Net-(J_SERVO_3-Pad3)") (class "Default")
      (node (ref "J_SERVO_3") (pin "3") (pinfunction "3_3") (pintype "passive"))
      (node (ref "R14") (pin "1") (pinfunction "1_1") (pintype "passive"))
    )
    (net (code "42") (name "Net-(J_SERVO_4-Pad3)") (class "Default")
      (node (ref "J_SERVO_4") (pin "3") (pinfunction "3_3") (pintype "passive"))
      (node (ref "R13") (pin "1") (pinfunction "1_1") (pintype "passive"))
    )
    (net (code "43") (name "Net-(Q3-IN)") (class "Default")
      (node (ref "C5") (pin "2") (pinfunction "2_2") (pintype "passive"))
      (node (ref "D2") (pin "C") (pinfunction "C_C") (pintype "passive"))
      (node (ref "L1") (pin "2") (pinfunction "2_2") (pintype "passive"))
      (node (ref "Q3") (pin "1") (pinfunction "IN_1") (pintype "input"))
    )
    (net (code "44") (name "Net-(V_STEPA-KL)") (class "Default")
      (node (ref "V_STEP") (pin "1") (pinfunction "KL_1") (pintype "passive"))
      (node (ref "X1") (pin "1") (pinfunction "KL_1") (pintype "passive"))
    )
    (net (code "45") (name "PWM_SERVO_1") (class "Default")
      (node (ref "IC2") (pin "1") (pinfunction "OUT_1") (pintype "output"))
      (node (ref "R1") (pin "2") (pinfunction "2_2") (pintype "passive"))
      (node (ref "R14") (pin "2") (pinfunction "2_2") (pintype "passive"))
    )
    (net (code "46") (name "PWM_SERVO_2") (class "Default")
      (node (ref "IC2") (pin "14") (pinfunction "OUT_14") (pintype "output"))
      (node (ref "R13") (pin "2") (pinfunction "2_2") (pintype "passive"))
      (node (ref "R4") (pin "2") (pinfunction "2_2") (pintype "passive"))
    )
    (net (code "47") (name "PWM_UC_SERVO_1") (class "Default")
      (node (ref "IC2") (pin "3") (pinfunction "+IN_3") (pintype "input"))
      (node (ref "R17") (pin "2") (pinfunction "2_2") (pintype "passive"))
    )
    (net (code "48") (name "PWM_UC_SERVO_2") (class "Default")
      (node (ref "IC2") (pin "12") (pinfunction "+IN_12") (pintype "input"))
      (node (ref "R16") (pin "2") (pinfunction "2_2") (pintype "passive"))
    )
    (net (code "49") (name "STEP_1") (class "Default")
      (node (ref "A4988_1") (pin "7") (pinfunction "STEP_7") (pintype "input"))
      (node (ref "BLUE_PILL1") (pin "P$32") (pinfunction "PA4_P$32") (pintype "bidirectional"))
    )
    (net (code "50") (name "STEP_2") (class "Default")
      (node (ref "A4988_2") (pin "7") (pinfunction "STEP_7") (pintype "input"))
      (node (ref "BLUE_PILL1") (pin "P$35") (pinfunction "PA1_P$35") (pintype "bidirectional"))
    )
    (net (code "51") (name "USART_RX") (class "Default")
      (node (ref "BLUE_PILL1") (pin "P$7") (pinfunction "PA10_P$7") (pintype "bidirectional"))
      (node (ref "J_USART") (pin "2") (pinfunction "2_2") (pintype "passive"))
    )
    (net (code "52") (name "USART_TX") (class "Default")
      (node (ref "BLUE_PILL1") (pin "P$6") (pinfunction "PA9_P$6") (pintype "bidirectional"))
      (node (ref "J_USART") (pin "1") (pinfunction "1_1") (pintype "passive"))
    )
    (net (code "53") (name "V_STEP") (class "Default")
      (node (ref "A4988_1") (pin "16") (pinfunction "VMOT_16") (pintype "power_in"))
      (node (ref "A4988_2") (pin "16") (pinfunction "VMOT_16") (pintype "power_in"))
      (node (ref "C1") (pin "+") (pinfunction "+_+") (pintype "passive"))
      (node (ref "C2") (pin "+") (pinfunction "+_+") (pintype "passive"))
      (node (ref "X1") (pin "2") (pinfunction "KL_2") (pintype "passive"))
    )
    (net (code "54") (name "unconnected-(BLUE_PILL1-3.3V1-PadP$20)") (class "Default")
      (node (ref "BLUE_PILL1") (pin "P$20") (pinfunction "3.3V1_P$20") (pintype "bidirectional"))
    )
    (net (code "55") (name "unconnected-(BLUE_PILL1-5V-PadP$18)") (class "Default")
      (node (ref "BLUE_PILL1") (pin "P$18") (pinfunction "5V_P$18") (pintype "bidirectional"))
    )
    (net (code "56") (name "unconnected-(BLUE_PILL1-GND2-PadP$19)") (class "Default")
      (node (ref "BLUE_PILL1") (pin "P$19") (pinfunction "GND2_P$19") (pintype "bidirectional"))
    )
    (net (code "57") (name "unconnected-(BLUE_PILL1-PA8-PadP$5)") (class "Default")
      (node (ref "BLUE_PILL1") (pin "P$5") (pinfunction "PA8_P$5") (pintype "bidirectional"))
    )
    (net (code "58") (name "unconnected-(BLUE_PILL1-PA11-PadP$8)") (class "Default")
      (node (ref "BLUE_PILL1") (pin "P$8") (pinfunction "PA11_P$8") (pintype "bidirectional"))
    )
    (net (code "59") (name "unconnected-(BLUE_PILL1-PA12-PadP$9)") (class "Default")
      (node (ref "BLUE_PILL1") (pin "P$9") (pinfunction "PA12_P$9") (pintype "bidirectional"))
    )
    (net (code "60") (name "unconnected-(BLUE_PILL1-PA15-PadP$10)") (class "Default")
      (node (ref "BLUE_PILL1") (pin "P$10") (pinfunction "PA15_P$10") (pintype "bidirectional"))
    )
    (net (code "61") (name "unconnected-(BLUE_PILL1-PB0-PadP$28)") (class "Default")
      (node (ref "BLUE_PILL1") (pin "P$28") (pinfunction "PB0_P$28") (pintype "bidirectional"))
    )
    (net (code "62") (name "unconnected-(BLUE_PILL1-PB1-PadP$27)") (class "Default")
      (node (ref "BLUE_PILL1") (pin "P$27") (pinfunction "PB1_P$27") (pintype "bidirectional"))
    )
    (net (code "63") (name "unconnected-(BLUE_PILL1-PB8-PadP$16)") (class "Default")
      (node (ref "BLUE_PILL1") (pin "P$16") (pinfunction "PB8_P$16") (pintype "bidirectional"))
    )
    (net (code "64") (name "unconnected-(BLUE_PILL1-PB9-PadP$17)") (class "Default")
      (node (ref "BLUE_PILL1") (pin "P$17") (pinfunction "PB9_P$17") (pintype "bidirectional"))
    )
    (net (code "65") (name "unconnected-(BLUE_PILL1-PB10-PadP$26)") (class "Default")
      (node (ref "BLUE_PILL1") (pin "P$26") (pinfunction "PB10_P$26") (pintype "bidirectional"))
    )
    (net (code "66") (name "unconnected-(BLUE_PILL1-PB11-PadP$25)") (class "Default")
      (node (ref "BLUE_PILL1") (pin "P$25") (pinfunction "PB11_P$25") (pintype "bidirectional"))
    )
    (net (code "67") (name "unconnected-(BLUE_PILL1-PB12-PadP$1)") (class "Default")
      (node (ref "BLUE_PILL1") (pin "P$1") (pinfunction "PB12_P$1") (pintype "bidirectional"))
    )
    (net (code "68") (name "unconnected-(BLUE_PILL1-PB13-PadP$2)") (class "Default")
      (node (ref "BLUE_PILL1") (pin "P$2") (pinfunction "PB13_P$2") (pintype "bidirectional"))
    )
    (net (code "69") (name "unconnected-(BLUE_PILL1-PB14-PadP$3)") (class "Default")
      (node (ref "BLUE_PILL1") (pin "P$3") (pinfunction "PB14_P$3") (pintype "bidirectional"))
    )
    (net (code "70") (name "unconnected-(BLUE_PILL1-PB15-PadP$4)") (class "Default")
      (node (ref "BLUE_PILL1") (pin "P$4") (pinfunction "PB15_P$4") (pintype "bidirectional"))
    )
    (net (code "71") (name "unconnected-(BLUE_PILL1-PC13-PadP$39)") (class "Default")
      (node (ref "BLUE_PILL1") (pin "P$39") (pinfunction "PC13_P$39") (pintype "bidirectional"))
    )
    (net (code "72") (name "unconnected-(BLUE_PILL1-PC14-PadP$38)") (class "Default")
      (node (ref "BLUE_PILL1") (pin "P$38") (pinfunction "PC14_P$38") (pintype "bidirectional"))
    )
    (net (code "73") (name "unconnected-(BLUE_PILL1-PC15-PadP$37)") (class "Default")
      (node (ref "BLUE_PILL1") (pin "P$37") (pinfunction "PC15_P$37") (pintype "bidirectional"))
    )
    (net (code "74") (name "unconnected-(BLUE_PILL1-RESET-PadP$24)") (class "Default")
      (node (ref "BLUE_PILL1") (pin "P$24") (pinfunction "RESET_P$24") (pintype "bidirectional"))
    )
    (net (code "75") (name "unconnected-(BLUE_PILL1-VBAT-PadP$40)") (class "Default")
      (node (ref "BLUE_PILL1") (pin "P$40") (pinfunction "VBAT_P$40") (pintype "bidirectional"))
    )
  )
)
